# PCard.net
KiCad netlist of a schematic drawn in Altium Designer
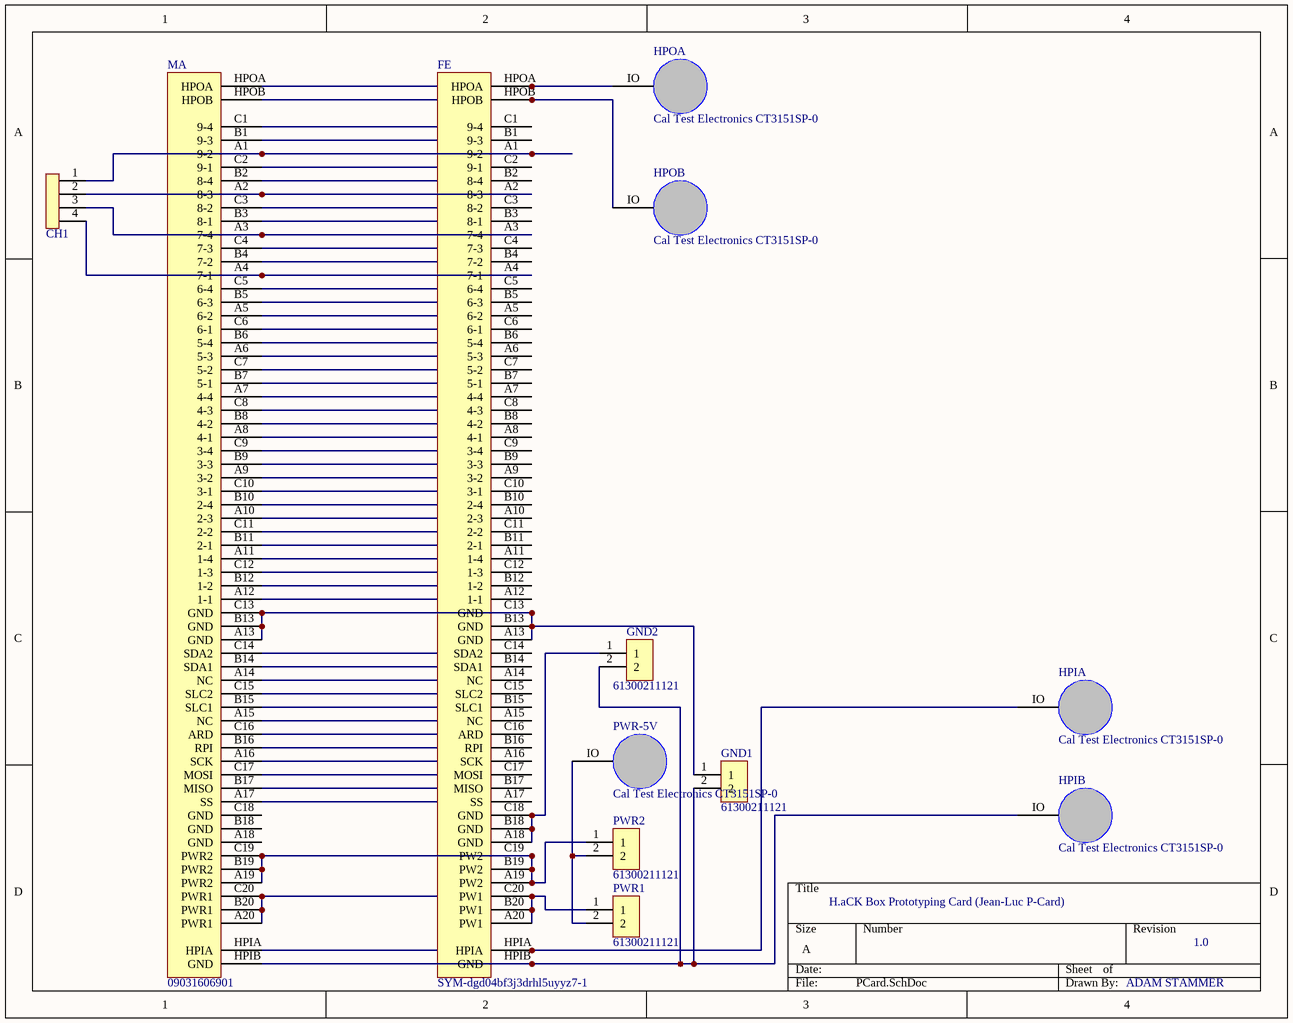
[diagram p0: PCard.SchDoc]

(export (version "E")
  (design (tool "Eeschema 10.0.6"))
  (components
    (comp (ref "CH1")
      (value "Molex 22-28-4043")
      (footprint "HEADER_1x4")
      (description "Conn; Rect./PCB; Breakaway Header; 4 Cir.; Vert.; KK 254 Ser.; Gold Plate; 6.09mm Pin L")
      (fields (field (name "MANUFACTURER PART NUMBER") "22-28-4043"))
      (libsource (lib "CommunityVault") (part "CMP-44448d4a5f9d9b83-3"))
    )
    (comp (ref "FE")
      (value "SYM-dgd04bf3j3drhl5uyyz7-1")
      (footprint "PCBComponent_1 - duplicate")
      (description "CONN DIN RCPT 64POS PCB GOLD")
      (libsource (lib "CommunityVault") (part "CMP-dgd04bf3j3drhl5uyyz7-22"))
    )
    (comp (ref "GND1")
      (value "61300211121")
      (footprint "PCB-omgsbkhp90n7lpri88og-1")
      (description "THT Vertical Pin Header WR-PHD, Pitch 2.54 mm, Single Row, 2 pins")
      (libsource (lib "CommunityVault") (part "CMP-748fbcb73d6bab48-27"))
    )
    (comp (ref "GND2")
      (value "61300211121")
      (footprint "PCB-omgsbkhp90n7lpri88og-1")
      (description "THT Vertical Pin Header WR-PHD, Pitch 2.54 mm, Single Row, 2 pins")
      (libsource (lib "CommunityVault") (part "CMP-748fbcb73d6bab48-27"))
    )
    (comp (ref "HPIA")
      (value "Cal Test Electronics CT3151SP-0")
      (footprint "PCB-y1ci8m7vwvotsse2jq9i-1")
      (description "4MM Safety Jack , Horizontal Pcb Mount Black")
      (libsource (lib "CommunityVault") (part "CMP-869a4c9259de595d-9"))
    )
    (comp (ref "HPIB")
      (value "Cal Test Electronics CT3151SP-0")
      (footprint "PCB-y1ci8m7vwvotsse2jq9i-1")
      (description "4MM Safety Jack , Horizontal Pcb Mount Black")
      (libsource (lib "CommunityVault") (part "CMP-869a4c9259de595d-9"))
    )
    (comp (ref "HPOA")
      (value "Cal Test Electronics CT3151SP-0")
      (footprint "PCB-y1ci8m7vwvotsse2jq9i-1")
      (description "4MM Safety Jack , Horizontal Pcb Mount Black")
      (libsource (lib "CommunityVault") (part "CMP-869a4c9259de595d-9"))
    )
    (comp (ref "HPOB")
      (value "Cal Test Electronics CT3151SP-0")
      (footprint "PCB-y1ci8m7vwvotsse2jq9i-1")
      (description "4MM Safety Jack , Horizontal Pcb Mount Black")
      (libsource (lib "CommunityVault") (part "CMP-869a4c9259de595d-9"))
    )
    (comp (ref "MA")
      (value "09031606901")
      (footprint "PCB-uzhe8vs3bcqz6bzs18qy-1")
      (description "Conn DIN 41612 M 60Power/4Coaxial POS 2.54mm Solder RA Thru-Hole")
      (libsource (lib "CommunityVault") (part "CMP-dd70146577e902b7-11"))
    )
    (comp (ref "PWR-5V")
      (value "Cal Test Electronics CT3151SP-0")
      (footprint "PCB-y1ci8m7vwvotsse2jq9i-1")
      (description "4MM Safety Jack , Horizontal Pcb Mount Black")
      (libsource (lib "CommunityVault") (part "CMP-869a4c9259de595d-9"))
    )
    (comp (ref "PWR1")
      (value "61300211121")
      (footprint "PCB-omgsbkhp90n7lpri88og-1")
      (description "THT Vertical Pin Header WR-PHD, Pitch 2.54 mm, Single Row, 2 pins")
      (libsource (lib "CommunityVault") (part "CMP-748fbcb73d6bab48-27"))
    )
    (comp (ref "PWR2")
      (value "61300211121")
      (footprint "PCB-omgsbkhp90n7lpri88og-1")
      (description "THT Vertical Pin Header WR-PHD, Pitch 2.54 mm, Single Row, 2 pins")
      (libsource (lib "CommunityVault") (part "CMP-748fbcb73d6bab48-27"))
    )
  )
  (nets
    (net (code "1") (name "Net-(FE-1-1)") (class "Default")
      (node (ref "FE") (pin "A12") (pinfunction "1-1_A12") (pintype "passive"))
      (node (ref "MA") (pin "A12") (pinfunction "1-1_A12") (pintype "passive"))
    )
    (net (code "2") (name "Net-(FE-1-2)") (class "Default")
      (node (ref "FE") (pin "B12") (pinfunction "1-2_B12") (pintype "passive"))
      (node (ref "MA") (pin "B12") (pinfunction "1-2_B12") (pintype "passive"))
    )
    (net (code "3") (name "Net-(FE-1-3)") (class "Default")
      (node (ref "FE") (pin "C12") (pinfunction "1-3_C12") (pintype "passive"))
      (node (ref "MA") (pin "C12") (pinfunction "1-3_C12") (pintype "passive"))
    )
    (net (code "4") (name "Net-(FE-1-4)") (class "Default")
      (node (ref "FE") (pin "A11") (pinfunction "1-4_A11") (pintype "passive"))
      (node (ref "MA") (pin "A11") (pinfunction "1-4_A11") (pintype "passive"))
    )
    (net (code "5") (name "Net-(FE-2-1)") (class "Default")
      (node (ref "FE") (pin "B11") (pinfunction "2-1_B11") (pintype "passive"))
      (node (ref "MA") (pin "B11") (pinfunction "2-1_B11") (pintype "passive"))
    )
    (net (code "6") (name "Net-(FE-2-2)") (class "Default")
      (node (ref "FE") (pin "C11") (pinfunction "2-2_C11") (pintype "passive"))
      (node (ref "MA") (pin "C11") (pinfunction "2-2_C11") (pintype "passive"))
    )
    (net (code "7") (name "Net-(FE-2-3)") (class "Default")
      (node (ref "FE") (pin "A10") (pinfunction "2-3_A10") (pintype "passive"))
      (node (ref "MA") (pin "A10") (pinfunction "2-3_A10") (pintype "passive"))
    )
    (net (code "8") (name "Net-(FE-2-4)") (class "Default")
      (node (ref "FE") (pin "B10") (pinfunction "2-4_B10") (pintype "passive"))
      (node (ref "MA") (pin "B10") (pinfunction "2-4_B10") (pintype "passive"))
    )
    (net (code "9") (name "Net-(FE-3-1)") (class "Default")
      (node (ref "FE") (pin "C10") (pinfunction "3-1_C10") (pintype "passive"))
      (node (ref "MA") (pin "C10") (pinfunction "3-1_C10") (pintype "passive"))
    )
    (net (code "10") (name "Net-(FE-3-2)") (class "Default")
      (node (ref "FE") (pin "A9") (pinfunction "3-2_A9") (pintype "passive"))
      (node (ref "MA") (pin "A9") (pinfunction "3-2_A9") (pintype "passive"))
    )
    (net (code "11") (name "Net-(FE-3-3)") (class "Default")
      (node (ref "FE") (pin "B9") (pinfunction "3-3_B9") (pintype "passive"))
      (node (ref "MA") (pin "B9") (pinfunction "3-3_B9") (pintype "passive"))
    )
    (net (code "12") (name "Net-(FE-3-4)") (class "Default")
      (node (ref "FE") (pin "C9") (pinfunction "3-4_C9") (pintype "passive"))
      (node (ref "MA") (pin "C9") (pinfunction "3-4_C9") (pintype "passive"))
    )
    (net (code "13") (name "Net-(FE-4-1)") (class "Default")
      (node (ref "FE") (pin "A8") (pinfunction "4-1_A8") (pintype "passive"))
      (node (ref "MA") (pin "A8") (pinfunction "4-1_A8") (pintype "passive"))
    )
    (net (code "14") (name "Net-(FE-4-2)") (class "Default")
      (node (ref "FE") (pin "B8") (pinfunction "4-2_B8") (pintype "passive"))
      (node (ref "MA") (pin "B8") (pinfunction "4-2_B8") (pintype "passive"))
    )
    (net (code "15") (name "Net-(FE-4-3)") (class "Default")
      (node (ref "FE") (pin "C8") (pinfunction "4-3_C8") (pintype "passive"))
      (node (ref "MA") (pin "C8") (pinfunction "4-3_C8") (pintype "passive"))
    )
    (net (code "16") (name "Net-(FE-4-4)") (class "Default")
      (node (ref "FE") (pin "A7") (pinfunction "4-4_A7") (pintype "passive"))
      (node (ref "MA") (pin "A7") (pinfunction "4-4_A7") (pintype "passive"))
    )
    (net (code "17") (name "Net-(FE-5-1)") (class "Default")
      (node (ref "FE") (pin "B7") (pinfunction "5-1_B7") (pintype "passive"))
      (node (ref "MA") (pin "B7") (pinfunction "5-1_B7") (pintype "passive"))
    )
    (net (code "18") (name "Net-(FE-5-2)") (class "Default")
      (node (ref "FE") (pin "C7") (pinfunction "5-2_C7") (pintype "passive"))
      (node (ref "MA") (pin "C7") (pinfunction "5-2_C7") (pintype "passive"))
    )
    (net (code "19") (name "Net-(FE-5-3)") (class "Default")
      (node (ref "FE") (pin "A6") (pinfunction "5-3_A6") (pintype "passive"))
      (node (ref "MA") (pin "A6") (pinfunction "5-3_A6") (pintype "passive"))
    )
    (net (code "20") (name "Net-(FE-5-4)") (class "Default")
      (node (ref "FE") (pin "B6") (pinfunction "5-4_B6") (pintype "passive"))
      (node (ref "MA") (pin "B6") (pinfunction "5-4_B6") (pintype "passive"))
    )
    (net (code "21") (name "Net-(FE-6-1)") (class "Default")
      (node (ref "FE") (pin "C6") (pinfunction "6-1_C6") (pintype "passive"))
      (node (ref "MA") (pin "C6") (pinfunction "6-1_C6") (pintype "passive"))
    )
    (net (code "22") (name "Net-(FE-6-2)") (class "Default")
      (node (ref "FE") (pin "A5") (pinfunction "6-2_A5") (pintype "passive"))
      (node (ref "MA") (pin "A5") (pinfunction "6-2_A5") (pintype "passive"))
    )
    (net (code "23") (name "Net-(FE-6-3)") (class "Default")
      (node (ref "FE") (pin "B5") (pinfunction "6-3_B5") (pintype "passive"))
      (node (ref "MA") (pin "B5") (pinfunction "6-3_B5") (pintype "passive"))
    )
    (net (code "24") (name "Net-(FE-6-4)") (class "Default")
      (node (ref "FE") (pin "C5") (pinfunction "6-4_C5") (pintype "passive"))
      (node (ref "MA") (pin "C5") (pinfunction "6-4_C5") (pintype "passive"))
    )
    (net (code "25") (name "Net-(FE-7-1)") (class "Default")
      (node (ref "CH1") (pin "4") (pinfunction "4_4") (pintype "passive"))
      (node (ref "FE") (pin "A4") (pinfunction "7-1_A4") (pintype "passive"))
      (node (ref "MA") (pin "A4") (pinfunction "7-1_A4") (pintype "passive"))
    )
    (net (code "26") (name "Net-(FE-7-2)") (class "Default")
      (node (ref "FE") (pin "B4") (pinfunction "7-2_B4") (pintype "passive"))
      (node (ref "MA") (pin "B4") (pinfunction "7-2_B4") (pintype "passive"))
    )
    (net (code "27") (name "Net-(FE-7-3)") (class "Default")
      (node (ref "FE") (pin "C4") (pinfunction "7-3_C4") (pintype "passive"))
      (node (ref "MA") (pin "C4") (pinfunction "7-3_C4") (pintype "passive"))
    )
    (net (code "28") (name "Net-(FE-7-4)") (class "Default")
      (node (ref "CH1") (pin "3") (pinfunction "3_3") (pintype "passive"))
      (node (ref "FE") (pin "A3") (pinfunction "7-4_A3") (pintype "passive"))
      (node (ref "MA") (pin "A3") (pinfunction "7-4_A3") (pintype "passive"))
    )
    (net (code "29") (name "Net-(FE-8-1)") (class "Default")
      (node (ref "FE") (pin "B3") (pinfunction "8-1_B3") (pintype "passive"))
      (node (ref "MA") (pin "B3") (pinfunction "8-1_B3") (pintype "passive"))
    )
    (net (code "30") (name "Net-(FE-8-2)") (class "Default")
      (node (ref "FE") (pin "C3") (pinfunction "8-2_C3") (pintype "passive"))
      (node (ref "MA") (pin "C3") (pinfunction "8-2_C3") (pintype "passive"))
    )
    (net (code "31") (name "Net-(FE-8-3)") (class "Default")
      (node (ref "CH1") (pin "2") (pinfunction "2_2") (pintype "passive"))
      (node (ref "FE") (pin "A2") (pinfunction "8-3_A2") (pintype "passive"))
      (node (ref "MA") (pin "A2") (pinfunction "8-3_A2") (pintype "passive"))
    )
    (net (code "32") (name "Net-(FE-8-4)") (class "Default")
      (node (ref "FE") (pin "B2") (pinfunction "8-4_B2") (pintype "passive"))
      (node (ref "MA") (pin "B2") (pinfunction "8-4_B2") (pintype "passive"))
    )
    (net (code "33") (name "Net-(FE-9-1)") (class "Default")
      (node (ref "FE") (pin "C2") (pinfunction "9-1_C2") (pintype "passive"))
      (node (ref "MA") (pin "C2") (pinfunction "9-1_C2") (pintype "passive"))
    )
    (net (code "34") (name "Net-(FE-9-2)") (class "Default")
      (node (ref "CH1") (pin "1") (pinfunction "1_1") (pintype "passive"))
      (node (ref "FE") (pin "A1") (pinfunction "9-2_A1") (pintype "passive"))
      (node (ref "MA") (pin "A1") (pinfunction "9-2_A1") (pintype "passive"))
    )
    (net (code "35") (name "Net-(FE-9-3)") (class "Default")
      (node (ref "FE") (pin "B1") (pinfunction "9-3_B1") (pintype "passive"))
      (node (ref "MA") (pin "B1") (pinfunction "9-3_B1") (pintype "passive"))
    )
    (net (code "36") (name "Net-(FE-9-4)") (class "Default")
      (node (ref "FE") (pin "C1") (pinfunction "9-4_C1") (pintype "passive"))
      (node (ref "MA") (pin "C1") (pinfunction "9-4_C1") (pintype "passive"))
    )
    (net (code "37") (name "Net-(FE-ARD)") (class "Default")
      (node (ref "FE") (pin "C16") (pinfunction "ARD_C16") (pintype "passive"))
      (node (ref "MA") (pin "C16") (pinfunction "ARD_C16") (pintype "passive"))
    )
    (net (code "38") (name "Net-(FE-GND-PadA13)") (class "Default")
      (node (ref "FE") (pin "A13") (pinfunction "GND_A13") (pintype "passive"))
      (node (ref "FE") (pin "B13") (pinfunction "GND_B13") (pintype "passive"))
      (node (ref "FE") (pin "C13") (pinfunction "GND_C13") (pintype "passive"))
      (node (ref "GND1") (pin "1") (pinfunction "1_1") (pintype "passive"))
      (node (ref "MA") (pin "A13") (pinfunction "GND_A13") (pintype "passive"))
      (node (ref "MA") (pin "B13") (pinfunction "GND_B13") (pintype "passive"))
      (node (ref "MA") (pin "C13") (pinfunction "GND_C13") (pintype "passive"))
    )
    (net (code "39") (name "Net-(FE-GND-PadA18)") (class "Default")
      (node (ref "FE") (pin "A18") (pinfunction "GND_A18") (pintype "passive"))
      (node (ref "FE") (pin "B18") (pinfunction "GND_B18") (pintype "passive"))
      (node (ref "FE") (pin "C18") (pinfunction "GND_C18") (pintype "passive"))
      (node (ref "GND2") (pin "1") (pinfunction "1_1") (pintype "passive"))
    )
    (net (code "40") (name "Net-(FE-GND-PadHPIB)") (class "Default")
      (node (ref "FE") (pin "HPIB") (pinfunction "GND_HPIB") (pintype "passive"))
      (node (ref "GND1") (pin "2") (pinfunction "2_2") (pintype "passive"))
      (node (ref "GND2") (pin "2") (pinfunction "2_2") (pintype "passive"))
      (node (ref "HPIB") (pin "IO") (pinfunction "IO_IO") (pintype "passive"))
      (node (ref "MA") (pin "HPIB") (pinfunction "GND_HPIB") (pintype "passive"))
    )
    (net (code "41") (name "Net-(FE-MISO)") (class "Default")
      (node (ref "FE") (pin "B17") (pinfunction "MISO_B17") (pintype "passive"))
      (node (ref "MA") (pin "B17") (pinfunction "MISO_B17") (pintype "passive"))
    )
    (net (code "42") (name "Net-(FE-MOSI)") (class "Default")
      (node (ref "FE") (pin "C17") (pinfunction "MOSI_C17") (pintype "passive"))
      (node (ref "MA") (pin "C17") (pinfunction "MOSI_C17") (pintype "passive"))
    )
    (net (code "43") (name "Net-(FE-NC-PadA14)") (class "Default")
      (node (ref "FE") (pin "A14") (pinfunction "NC_A14") (pintype "passive"))
      (node (ref "MA") (pin "A14") (pinfunction "NC_A14") (pintype "passive"))
    )
    (net (code "44") (name "Net-(FE-NC-PadA15)") (class "Default")
      (node (ref "FE") (pin "A15") (pinfunction "NC_A15") (pintype "passive"))
      (node (ref "MA") (pin "A15") (pinfunction "NC_A15") (pintype "passive"))
    )
    (net (code "45") (name "Net-(FE-PW1-PadA20)") (class "Default")
      (node (ref "FE") (pin "A20") (pinfunction "PW1_A20") (pintype "passive"))
      (node (ref "FE") (pin "B20") (pinfunction "PW1_B20") (pintype "passive"))
      (node (ref "FE") (pin "C20") (pinfunction "PW1_C20") (pintype "passive"))
      (node (ref "MA") (pin "A20") (pinfunction "PWR1_A20") (pintype "passive"))
      (node (ref "MA") (pin "B20") (pinfunction "PWR1_B20") (pintype "passive"))
      (node (ref "MA") (pin "C20") (pinfunction "PWR1_C20") (pintype "passive"))
      (node (ref "PWR1") (pin "1") (pinfunction "1_1") (pintype "passive"))
    )
    (net (code "46") (name "Net-(FE-PW2-PadA19)") (class "Default")
      (node (ref "FE") (pin "A19") (pinfunction "PW2_A19") (pintype "passive"))
      (node (ref "FE") (pin "B19") (pinfunction "PW2_B19") (pintype "passive"))
      (node (ref "FE") (pin "C19") (pinfunction "PW2_C19") (pintype "passive"))
      (node (ref "MA") (pin "A19") (pinfunction "PWR2_A19") (pintype "passive"))
      (node (ref "MA") (pin "B19") (pinfunction "PWR2_B19") (pintype "passive"))
      (node (ref "MA") (pin "C19") (pinfunction "PWR2_C19") (pintype "passive"))
      (node (ref "PWR2") (pin "1") (pinfunction "1_1") (pintype "passive"))
    )
    (net (code "47") (name "Net-(FE-PadHPIA)") (class "Default")
      (node (ref "FE") (pin "HPIA") (pinfunction "HPIA_HPIA") (pintype "passive"))
      (node (ref "HPIA") (pin "IO") (pinfunction "IO_IO") (pintype "passive"))
      (node (ref "MA") (pin "HPIA") (pinfunction "HPIA_HPIA") (pintype "passive"))
    )
    (net (code "48") (name "Net-(FE-PadHPOA)") (class "Default")
      (node (ref "FE") (pin "HPOA") (pinfunction "HPOA_HPOA") (pintype "passive"))
      (node (ref "HPOA") (pin "IO") (pinfunction "IO_IO") (pintype "passive"))
      (node (ref "MA") (pin "HPOA") (pinfunction "HPOA_HPOA") (pintype "passive"))
    )
    (net (code "49") (name "Net-(FE-PadHPOB)") (class "Default")
      (node (ref "FE") (pin "HPOB") (pinfunction "HPOB_HPOB") (pintype "passive"))
      (node (ref "HPOB") (pin "IO") (pinfunction "IO_IO") (pintype "passive"))
      (node (ref "MA") (pin "HPOB") (pinfunction "HPOB_HPOB") (pintype "passive"))
    )
    (net (code "50") (name "Net-(FE-RPI)") (class "Default")
      (node (ref "FE") (pin "B16") (pinfunction "RPI_B16") (pintype "passive"))
      (node (ref "MA") (pin "B16") (pinfunction "RPI_B16") (pintype "passive"))
    )
    (net (code "51") (name "Net-(FE-SCK)") (class "Default")
      (node (ref "FE") (pin "A16") (pinfunction "SCK_A16") (pintype "passive"))
      (node (ref "MA") (pin "A16") (pinfunction "SCK_A16") (pintype "passive"))
    )
    (net (code "52") (name "Net-(FE-SDA1)") (class "Default")
      (node (ref "FE") (pin "B14") (pinfunction "SDA1_B14") (pintype "passive"))
      (node (ref "MA") (pin "B14") (pinfunction "SDA1_B14") (pintype "passive"))
    )
    (net (code "53") (name "Net-(FE-SDA2)") (class "Default")
      (node (ref "FE") (pin "C14") (pinfunction "SDA2_C14") (pintype "passive"))
      (node (ref "MA") (pin "C14") (pinfunction "SDA2_C14") (pintype "passive"))
    )
    (net (code "54") (name "Net-(FE-SLC1)") (class "Default")
      (node (ref "FE") (pin "B15") (pinfunction "SLC1_B15") (pintype "passive"))
      (node (ref "MA") (pin "B15") (pinfunction "SLC1_B15") (pintype "passive"))
    )
    (net (code "55") (name "Net-(FE-SLC2)") (class "Default")
      (node (ref "FE") (pin "C15") (pinfunction "SLC2_C15") (pintype "passive"))
      (node (ref "MA") (pin "C15") (pinfunction "SLC2_C15") (pintype "passive"))
    )
    (net (code "56") (name "Net-(FE-SS)") (class "Default")
      (node (ref "FE") (pin "A17") (pinfunction "SS_A17") (pintype "passive"))
      (node (ref "MA") (pin "A17") (pinfunction "SS_A17") (pintype "passive"))
    )
    (net (code "57") (name "Net-(PWR-5V-PadIO)") (class "Default")
      (node (ref "PWR-5V") (pin "IO") (pinfunction "IO_IO") (pintype "passive"))
      (node (ref "PWR1") (pin "2") (pinfunction "2_2") (pintype "passive"))
      (node (ref "PWR2") (pin "2") (pinfunction "2_2") (pintype "passive"))
    )
    (net (code "58") (name "unconnected-(MA-GND-PadA18)") (class "Default")
      (node (ref "MA") (pin "A18") (pinfunction "GND_A18") (pintype "passive"))
    )
    (net (code "59") (name "unconnected-(MA-GND-PadB18)") (class "Default")
      (node (ref "MA") (pin "B18") (pinfunction "GND_B18") (pintype "passive"))
    )
    (net (code "60") (name "unconnected-(MA-GND-PadC18)") (class "Default")
      (node (ref "MA") (pin "C18") (pinfunction "GND_C18") (pintype "passive"))
    )
  )
)
